# design.net
KiCad netlist of a schematic drawn in Altium Designer
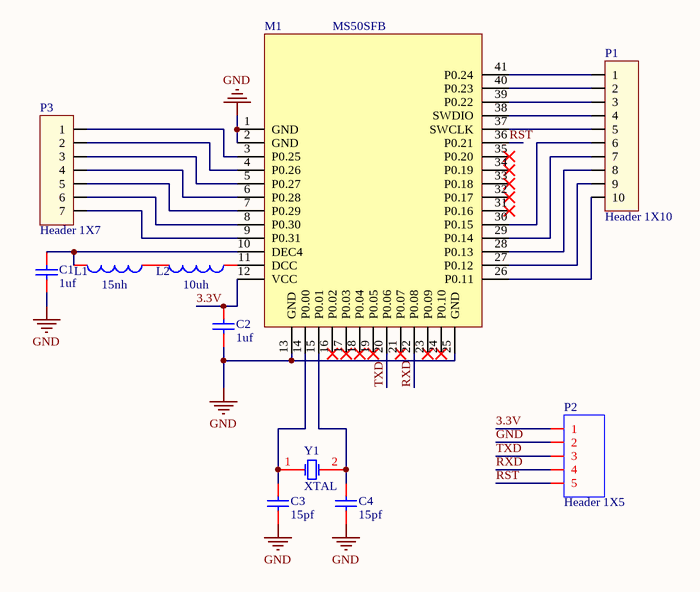
[diagram p0: 蓝牙板.SchDoc]

(export (version "E")
  (design (tool "Eeschema 10.0.6"))
  (components
    (comp (ref "C1") (value "1uf") (footprint "CAP[0603]") (libsource (lib "Jeil IT") (part "Cap")))
    (comp (ref "C2") (value "1uf") (footprint "CAP[0603]") (libsource (lib "Jeil IT") (part "Cap")))
    (comp (ref "C3") (value "15pf") (footprint "CAP[0603]") (libsource (lib "Jeil IT") (part "Cap")))
    (comp (ref "C4") (value "15pf") (footprint "CAP[0603]") (libsource (lib "Jeil IT") (part "Cap")))
    (comp (ref "L1") (value "15nh") (footprint "0603_L") (libsource (lib "Jeil IT") (part "inductor")))
    (comp (ref "L2") (value "10uh") (footprint "0603_L") (libsource (lib "Jeil IT") (part "inductor")))
    (comp (ref "M1")
      (value "MS50SFB")
      (footprint "MS50SFB_V3.0")
      (libsource (lib "module") (part "MS50SFB_V3.0"))
    )
    (comp (ref "P1")
      (value "Header 1X10")
      (footprint "HEADER 1X10")
      (libsource (lib "Jeil IT") (part "Header 1X10"))
    )
    (comp (ref "P2")
      (value "Header 1X5")
      (footprint "HEADER 1X5")
      (libsource (lib "Jeil IT") (part "Header 1X5"))
    )
    (comp (ref "P3")
      (value "Header 1X7")
      (footprint "HEADER 1X7")
      (libsource (lib "Jeil IT") (part "Header 1X7"))
    )
    (comp (ref "Y1") (value "XTAL") (footprint "XTAL-3215") (libsource (lib "Jeil IT") (part "XTAL")))
  )
  (nets
    (net (code "1") (name "/3.3V") (class "Default")
      (node (ref "C2") (pin "2") (pinfunction "2_2") (pintype "passive"))
      (node (ref "M1") (pin "12") (pinfunction "VCC_12") (pintype "passive"))
      (node (ref "P2") (pin "1") (pinfunction "1_1") (pintype "passive"))
    )
    (net (code "2") (name "/RST") (class "Default")
      (node (ref "M1") (pin "36") (pinfunction "P0.21_36") (pintype "passive"))
      (node (ref "P2") (pin "5") (pinfunction "5_5") (pintype "passive"))
    )
    (net (code "3") (name "/RXD") (class "Default")
      (node (ref "M1") (pin "22") (pinfunction "P0.08_22") (pintype "passive"))
      (node (ref "P2") (pin "4") (pinfunction "4_4") (pintype "passive"))
    )
    (net (code "4") (name "/TXD") (class "Default")
      (node (ref "M1") (pin "20") (pinfunction "P0.06_20") (pintype "passive"))
      (node (ref "P2") (pin "3") (pinfunction "3_3") (pintype "passive"))
    )
    (net (code "5") (name "GND") (class "Default")
      (node (ref "C1") (pin "1") (pinfunction "1_1") (pintype "passive"))
      (node (ref "C2") (pin "1") (pinfunction "1_1") (pintype "passive"))
      (node (ref "C3") (pin "1") (pinfunction "1_1") (pintype "passive"))
      (node (ref "C4") (pin "1") (pinfunction "1_1") (pintype "passive"))
      (node (ref "M1") (pin "1") (pinfunction "GND_1") (pintype "passive"))
      (node (ref "M1") (pin "13") (pinfunction "GND_13") (pintype "passive"))
      (node (ref "M1") (pin "2") (pinfunction "GND_2") (pintype "passive"))
      (node (ref "M1") (pin "25") (pinfunction "GND_25") (pintype "passive"))
      (node (ref "P2") (pin "2") (pinfunction "2_2") (pintype "passive"))
    )
    (net (code "6") (name "Net-(L1-Pad1)") (class "Default")
      (node (ref "L1") (pin "1") (pinfunction "1_1") (pintype "passive"))
      (node (ref "L2") (pin "2") (pinfunction "2_2") (pintype "passive"))
    )
    (net (code "7") (name "Net-(M1-DCC)") (class "Default")
      (node (ref "L2") (pin "1") (pinfunction "1_1") (pintype "passive"))
      (node (ref "M1") (pin "11") (pinfunction "DCC_11") (pintype "passive"))
    )
    (net (code "8") (name "Net-(M1-DEC4)") (class "Default")
      (node (ref "C1") (pin "2") (pinfunction "2_2") (pintype "passive"))
      (node (ref "L1") (pin "2") (pinfunction "2_2") (pintype "passive"))
      (node (ref "M1") (pin "10") (pinfunction "DEC4_10") (pintype "passive"))
    )
    (net (code "9") (name "Net-(M1-P0.00)") (class "Default")
      (node (ref "C3") (pin "2") (pinfunction "2_2") (pintype "passive"))
      (node (ref "M1") (pin "14") (pinfunction "P0.00_14") (pintype "passive"))
      (node (ref "Y1") (pin "1") (pinfunction "OSC1_1") (pintype "passive"))
    )
    (net (code "10") (name "Net-(M1-P0.01)") (class "Default")
      (node (ref "C4") (pin "2") (pinfunction "2_2") (pintype "passive"))
      (node (ref "M1") (pin "15") (pinfunction "P0.01_15") (pintype "passive"))
      (node (ref "Y1") (pin "2") (pinfunction "OSC2_2") (pintype "passive"))
    )
    (net (code "11") (name "Net-(M1-P0.11)") (class "Default")
      (node (ref "M1") (pin "26") (pinfunction "P0.11_26") (pintype "passive"))
      (node (ref "P1") (pin "10") (pinfunction "10_10") (pintype "passive"))
    )
    (net (code "12") (name "Net-(M1-P0.12)") (class "Default")
      (node (ref "M1") (pin "27") (pinfunction "P0.12_27") (pintype "passive"))
      (node (ref "P1") (pin "9") (pinfunction "9_9") (pintype "passive"))
    )
    (net (code "13") (name "Net-(M1-P0.13)") (class "Default")
      (node (ref "M1") (pin "28") (pinfunction "P0.13_28") (pintype "passive"))
      (node (ref "P1") (pin "8") (pinfunction "8_8") (pintype "passive"))
    )
    (net (code "14") (name "Net-(M1-P0.14)") (class "Default")
      (node (ref "M1") (pin "29") (pinfunction "P0.14_29") (pintype "passive"))
      (node (ref "P1") (pin "7") (pinfunction "7_7") (pintype "passive"))
    )
    (net (code "15") (name "Net-(M1-P0.15)") (class "Default")
      (node (ref "M1") (pin "30") (pinfunction "P0.15_30") (pintype "passive"))
      (node (ref "P1") (pin "6") (pinfunction "6_6") (pintype "passive"))
    )
    (net (code "16") (name "Net-(M1-P0.22)") (class "Default")
      (node (ref "M1") (pin "39") (pinfunction "P0.22_39") (pintype "passive"))
      (node (ref "P1") (pin "3") (pinfunction "3_3") (pintype "passive"))
    )
    (net (code "17") (name "Net-(M1-P0.23)") (class "Default")
      (node (ref "M1") (pin "40") (pinfunction "P0.23_40") (pintype "passive"))
      (node (ref "P1") (pin "2") (pinfunction "2_2") (pintype "passive"))
    )
    (net (code "18") (name "Net-(M1-P0.24)") (class "Default")
      (node (ref "M1") (pin "41") (pinfunction "P0.24_41") (pintype "passive"))
      (node (ref "P1") (pin "1") (pinfunction "1_1") (pintype "passive"))
    )
    (net (code "19") (name "Net-(M1-P0.25)") (class "Default")
      (node (ref "M1") (pin "3") (pinfunction "P0.25_3") (pintype "passive"))
      (node (ref "P3") (pin "1") (pinfunction "1_1") (pintype "passive"))
    )
    (net (code "20") (name "Net-(M1-P0.26)") (class "Default")
      (node (ref "M1") (pin "4") (pinfunction "P0.26_4") (pintype "passive"))
      (node (ref "P3") (pin "2") (pinfunction "2_2") (pintype "passive"))
    )
    (net (code "21") (name "Net-(M1-P0.27)") (class "Default")
      (node (ref "M1") (pin "5") (pinfunction "P0.27_5") (pintype "passive"))
      (node (ref "P3") (pin "3") (pinfunction "3_3") (pintype "passive"))
    )
    (net (code "22") (name "Net-(M1-P0.28)") (class "Default")
      (node (ref "M1") (pin "6") (pinfunction "P0.28_6") (pintype "passive"))
      (node (ref "P3") (pin "4") (pinfunction "4_4") (pintype "passive"))
    )
    (net (code "23") (name "Net-(M1-P0.29)") (class "Default")
      (node (ref "M1") (pin "7") (pinfunction "P0.29_7") (pintype "passive"))
      (node (ref "P3") (pin "5") (pinfunction "5_5") (pintype "passive"))
    )
    (net (code "24") (name "Net-(M1-P0.30)") (class "Default")
      (node (ref "M1") (pin "8") (pinfunction "P0.30_8") (pintype "passive"))
      (node (ref "P3") (pin "6") (pinfunction "6_6") (pintype "passive"))
    )
    (net (code "25") (name "Net-(M1-P0.31)") (class "Default")
      (node (ref "M1") (pin "9") (pinfunction "P0.31_9") (pintype "passive"))
      (node (ref "P3") (pin "7") (pinfunction "7_7") (pintype "passive"))
    )
    (net (code "26") (name "Net-(M1-SWCLK)") (class "Default")
      (node (ref "M1") (pin "37") (pinfunction "SWCLK_37") (pintype "passive"))
      (node (ref "P1") (pin "5") (pinfunction "5_5") (pintype "passive"))
    )
    (net (code "27") (name "Net-(M1-SWDIO)") (class "Default")
      (node (ref "M1") (pin "38") (pinfunction "SWDIO_38") (pintype "passive"))
      (node (ref "P1") (pin "4") (pinfunction "4_4") (pintype "passive"))
    )
    (net (code "28") (name "unconnected-(M1-P0.02-Pad16)") (class "Default")
      (node (ref "M1") (pin "16") (pinfunction "P0.02_16") (pintype "passive+no_connect"))
    )
    (net (code "29") (name "unconnected-(M1-P0.03-Pad17)") (class "Default")
      (node (ref "M1") (pin "17") (pinfunction "P0.03_17") (pintype "passive+no_connect"))
    )
    (net (code "30") (name "unconnected-(M1-P0.04-Pad18)") (class "Default")
      (node (ref "M1") (pin "18") (pinfunction "P0.04_18") (pintype "passive+no_connect"))
    )
    (net (code "31") (name "unconnected-(M1-P0.05-Pad19)") (class "Default")
      (node (ref "M1") (pin "19") (pinfunction "P0.05_19") (pintype "passive+no_connect"))
    )
    (net (code "32") (name "unconnected-(M1-P0.07-Pad21)") (class "Default")
      (node (ref "M1") (pin "21") (pinfunction "P0.07_21") (pintype "passive+no_connect"))
    )
    (net (code "33") (name "unconnected-(M1-P0.09-Pad23)") (class "Default")
      (node (ref "M1") (pin "23") (pinfunction "P0.09_23") (pintype "passive+no_connect"))
    )
    (net (code "34") (name "unconnected-(M1-P0.10-Pad24)") (class "Default")
      (node (ref "M1") (pin "24") (pinfunction "P0.10_24") (pintype "passive+no_connect"))
    )
    (net (code "35") (name "unconnected-(M1-P0.16-Pad31)") (class "Default")
      (node (ref "M1") (pin "31") (pinfunction "P0.16_31") (pintype "passive+no_connect"))
    )
    (net (code "36") (name "unconnected-(M1-P0.17-Pad32)") (class "Default")
      (node (ref "M1") (pin "32") (pinfunction "P0.17_32") (pintype "passive+no_connect"))
    )
    (net (code "37") (name "unconnected-(M1-P0.18-Pad33)") (class "Default")
      (node (ref "M1") (pin "33") (pinfunction "P0.18_33") (pintype "passive+no_connect"))
    )
    (net (code "38") (name "unconnected-(M1-P0.19-Pad34)") (class "Default")
      (node (ref "M1") (pin "34") (pinfunction "P0.19_34") (pintype "passive+no_connect"))
    )
    (net (code "39") (name "unconnected-(M1-P0.20-Pad35)") (class "Default")
      (node (ref "M1") (pin "35") (pinfunction "P0.20_35") (pintype "passive+no_connect"))
    )
  )
)
